# ProPrj_measure_boardd_2025-03-12.net
KiCad netlist of a schematic drawn in EasyEDA Pro
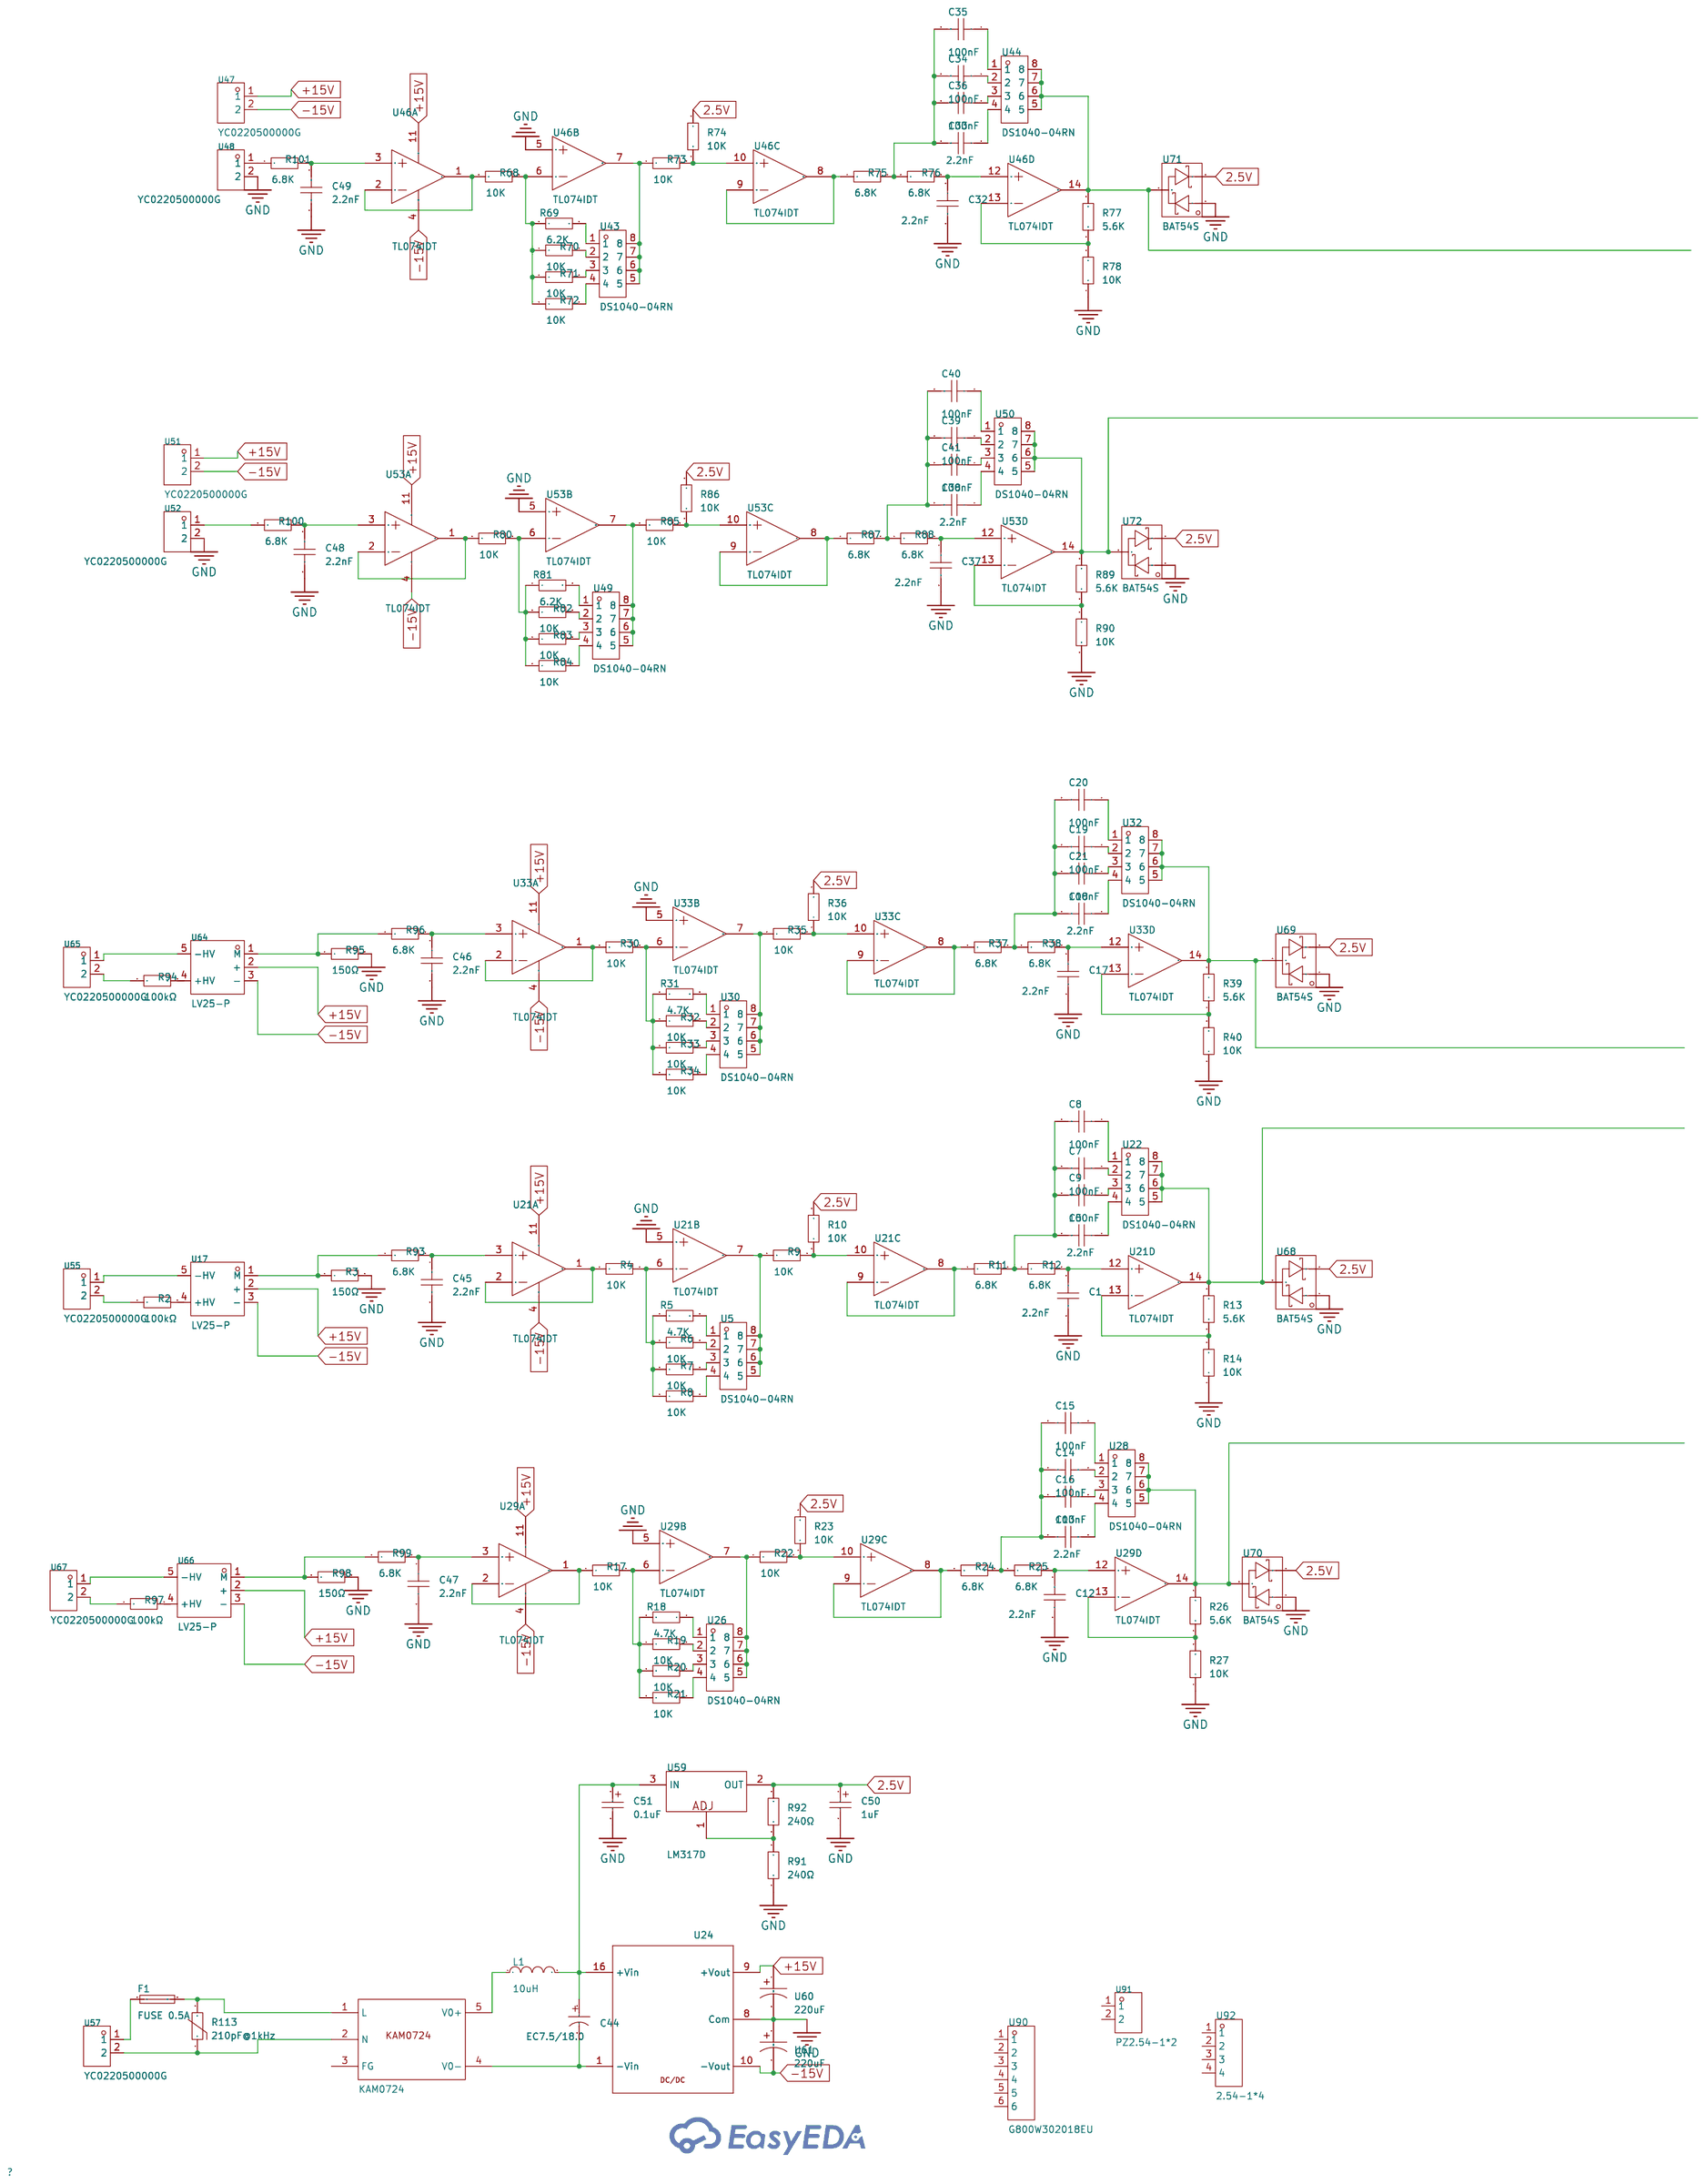
[diagram p0: schematic sheet]

(export (version "E")
  (design (tool "Eeschema 10.0.6"))
  (components
    (comp (ref "C1")
      (value "2.2nF")
      (footprint "easyedapro:C0805")
      (libsource (lib "easyedapro") (part "CAP"))
    )
    (comp (ref "C5")
      (value "2.2nF")
      (footprint "easyedapro:C0805")
      (libsource (lib "easyedapro") (part "CAP"))
    )
    (comp (ref "C7")
      (value "100nF")
      (footprint "easyedapro:C0805")
      (libsource (lib "easyedapro") (part "CAP"))
    )
    (comp (ref "C8")
      (value "100nF")
      (footprint "easyedapro:C0805")
      (libsource (lib "easyedapro") (part "CAP"))
    )
    (comp (ref "C9")
      (value "100nF")
      (footprint "easyedapro:C0805")
      (libsource (lib "easyedapro") (part "CAP"))
    )
    (comp (ref "C12")
      (value "2.2nF")
      (footprint "easyedapro:C0805")
      (libsource (lib "easyedapro") (part "CAP"))
    )
    (comp (ref "C13")
      (value "2.2nF")
      (footprint "easyedapro:C0805")
      (libsource (lib "easyedapro") (part "CAP"))
    )
    (comp (ref "C14")
      (value "100nF")
      (footprint "easyedapro:C0805")
      (libsource (lib "easyedapro") (part "CAP"))
    )
    (comp (ref "C15")
      (value "100nF")
      (footprint "easyedapro:C0805")
      (libsource (lib "easyedapro") (part "CAP"))
    )
    (comp (ref "C16")
      (value "100nF")
      (footprint "easyedapro:C0805")
      (libsource (lib "easyedapro") (part "CAP"))
    )
    (comp (ref "C17")
      (value "2.2nF")
      (footprint "easyedapro:C0805")
      (libsource (lib "easyedapro") (part "CAP"))
    )
    (comp (ref "C18")
      (value "2.2nF")
      (footprint "easyedapro:C0805")
      (libsource (lib "easyedapro") (part "CAP"))
    )
    (comp (ref "C19")
      (value "100nF")
      (footprint "easyedapro:C0805")
      (libsource (lib "easyedapro") (part "CAP"))
    )
    (comp (ref "C20")
      (value "100nF")
      (footprint "easyedapro:C0805")
      (libsource (lib "easyedapro") (part "CAP"))
    )
    (comp (ref "C21")
      (value "100nF")
      (footprint "easyedapro:C0805")
      (libsource (lib "easyedapro") (part "CAP"))
    )
    (comp (ref "C32")
      (value "2.2nF")
      (footprint "easyedapro:C0805")
      (libsource (lib "easyedapro") (part "CAP"))
    )
    (comp (ref "C33")
      (value "2.2nF")
      (footprint "easyedapro:C0805")
      (libsource (lib "easyedapro") (part "CAP"))
    )
    (comp (ref "C34")
      (value "100nF")
      (footprint "easyedapro:C0805")
      (libsource (lib "easyedapro") (part "CAP"))
    )
    (comp (ref "C35")
      (value "100nF")
      (footprint "easyedapro:C0805")
      (libsource (lib "easyedapro") (part "CAP"))
    )
    (comp (ref "C36")
      (value "100nF")
      (footprint "easyedapro:C0805")
      (libsource (lib "easyedapro") (part "CAP"))
    )
    (comp (ref "C37")
      (value "2.2nF")
      (footprint "easyedapro:C0805")
      (libsource (lib "easyedapro") (part "CAP"))
    )
    (comp (ref "C38")
      (value "2.2nF")
      (footprint "easyedapro:C0805")
      (libsource (lib "easyedapro") (part "CAP"))
    )
    (comp (ref "C39")
      (value "100nF")
      (footprint "easyedapro:C0805")
      (libsource (lib "easyedapro") (part "CAP"))
    )
    (comp (ref "C40")
      (value "100nF")
      (footprint "easyedapro:C0805")
      (libsource (lib "easyedapro") (part "CAP"))
    )
    (comp (ref "C41")
      (value "100nF")
      (footprint "easyedapro:C0805")
      (libsource (lib "easyedapro") (part "CAP"))
    )
    (comp (ref "C44")
      (value "EC7.5/18.0")
      (footprint "easyedapro:CAP-TH_BD18.0-P7.50-D1.2-FD")
      (libsource (lib "easyedapro") (part "EC7.5/18.0"))
    )
    (comp (ref "C45")
      (value "2.2nF")
      (footprint "easyedapro:C0805")
      (libsource (lib "easyedapro") (part "CAP"))
    )
    (comp (ref "C46")
      (value "2.2nF")
      (footprint "easyedapro:C0805")
      (libsource (lib "easyedapro") (part "CAP"))
    )
    (comp (ref "C47")
      (value "2.2nF")
      (footprint "easyedapro:C0805")
      (libsource (lib "easyedapro") (part "CAP"))
    )
    (comp (ref "C48")
      (value "2.2nF")
      (footprint "easyedapro:C0805")
      (libsource (lib "easyedapro") (part "CAP"))
    )
    (comp (ref "C49")
      (value "2.2nF")
      (footprint "easyedapro:C0805")
      (libsource (lib "easyedapro") (part "CAP"))
    )
    (comp (ref "C50")
      (value "1uF")
      (footprint "easyedapro:CAP-SMD_BD4.0-L4.3-W4.3-FD")
      (libsource (lib "easyedapro") (part "C_Ele_SMD"))
    )
    (comp (ref "C51")
      (value "0.1uF")
      (footprint "easyedapro:CAP-SMD_BD4.0-L4.3-W4.3-FD")
      (libsource (lib "easyedapro") (part "C_Ele_SMD"))
    )
    (comp (ref "F1")
      (value "FUSE 0.5A")
      (footprint "easyedapro:FUSE-TH_L8.5-W4.0-P5.08-D0.6")
      (fields (field (name "Manufacturer Part") "SQT3.15M") (field (name "Manufacturer") "TLC(竞沃)"))
      (libsource (lib "easyedapro") (part "FUSE 0.5A"))
    )
    (comp (ref "L1") (value "10uH") (footprint "easyedapro:L0805") (libsource (lib "easyedapro") (part "电感")))
    (comp (ref "R2")
      (value "100kΩ")
      (footprint "easyedapro:RES-TH_BD8.0-L24.5-P28.50-D0.8")
      (libsource (lib "easyedapro") (part "Res"))
    )
    (comp (ref "R3")
      (value "150Ω")
      (footprint "easyedapro:RES-TH_BD8.0-L24.5-P28.50-D0.8")
      (libsource (lib "easyedapro") (part "Res"))
    )
    (comp (ref "R4")
      (value "10K")
      (footprint "easyedapro:RES-TH_BD8.0-L24.5-P28.50-D0.8")
      (libsource (lib "easyedapro") (part "Res"))
    )
    (comp (ref "R5")
      (value "4.7K")
      (footprint "easyedapro:RES-TH_BD8.0-L24.5-P28.50-D0.8")
      (libsource (lib "easyedapro") (part "Res"))
    )
    (comp (ref "R6")
      (value "10K")
      (footprint "easyedapro:RES-TH_BD8.0-L24.5-P28.50-D0.8")
      (libsource (lib "easyedapro") (part "Res"))
    )
    (comp (ref "R7")
      (value "10K")
      (footprint "easyedapro:RES-TH_BD8.0-L24.5-P28.50-D0.8")
      (libsource (lib "easyedapro") (part "Res"))
    )
    (comp (ref "R8")
      (value "10K")
      (footprint "easyedapro:RES-TH_BD8.0-L24.5-P28.50-D0.8")
      (libsource (lib "easyedapro") (part "Res"))
    )
    (comp (ref "R9")
      (value "10K")
      (footprint "easyedapro:RES-TH_BD8.0-L24.5-P28.50-D0.8")
      (libsource (lib "easyedapro") (part "Res"))
    )
    (comp (ref "R10")
      (value "10K")
      (footprint "easyedapro:RES-TH_BD8.0-L24.5-P28.50-D0.8")
      (libsource (lib "easyedapro") (part "Res"))
    )
    (comp (ref "R11")
      (value "6.8K")
      (footprint "easyedapro:RES-TH_BD8.0-L24.5-P28.50-D0.8")
      (libsource (lib "easyedapro") (part "Res"))
    )
    (comp (ref "R12")
      (value "6.8K")
      (footprint "easyedapro:RES-TH_BD8.0-L24.5-P28.50-D0.8")
      (libsource (lib "easyedapro") (part "Res"))
    )
    (comp (ref "R13")
      (value "5.6K")
      (footprint "easyedapro:RES-TH_BD8.0-L24.5-P28.50-D0.8")
      (libsource (lib "easyedapro") (part "Res"))
    )
    (comp (ref "R14")
      (value "10K")
      (footprint "easyedapro:RES-TH_BD8.0-L24.5-P28.50-D0.8")
      (libsource (lib "easyedapro") (part "Res"))
    )
    (comp (ref "R17")
      (value "10K")
      (footprint "easyedapro:RES-TH_BD8.0-L24.5-P28.50-D0.8")
      (libsource (lib "easyedapro") (part "Res"))
    )
    (comp (ref "R18")
      (value "4.7K")
      (footprint "easyedapro:RES-TH_BD8.0-L24.5-P28.50-D0.8")
      (libsource (lib "easyedapro") (part "Res"))
    )
    (comp (ref "R19")
      (value "10K")
      (footprint "easyedapro:RES-TH_BD8.0-L24.5-P28.50-D0.8")
      (libsource (lib "easyedapro") (part "Res"))
    )
    (comp (ref "R20")
      (value "10K")
      (footprint "easyedapro:RES-TH_BD8.0-L24.5-P28.50-D0.8")
      (libsource (lib "easyedapro") (part "Res"))
    )
    (comp (ref "R21")
      (value "10K")
      (footprint "easyedapro:RES-TH_BD8.0-L24.5-P28.50-D0.8")
      (libsource (lib "easyedapro") (part "Res"))
    )
    (comp (ref "R22")
      (value "10K")
      (footprint "easyedapro:RES-TH_BD8.0-L24.5-P28.50-D0.8")
      (libsource (lib "easyedapro") (part "Res"))
    )
    (comp (ref "R23")
      (value "10K")
      (footprint "easyedapro:RES-TH_BD8.0-L24.5-P28.50-D0.8")
      (libsource (lib "easyedapro") (part "Res"))
    )
    (comp (ref "R24")
      (value "6.8K")
      (footprint "easyedapro:RES-TH_BD8.0-L24.5-P28.50-D0.8")
      (libsource (lib "easyedapro") (part "Res"))
    )
    (comp (ref "R25")
      (value "6.8K")
      (footprint "easyedapro:RES-TH_BD8.0-L24.5-P28.50-D0.8")
      (libsource (lib "easyedapro") (part "Res"))
    )
    (comp (ref "R26")
      (value "5.6K")
      (footprint "easyedapro:RES-TH_BD8.0-L24.5-P28.50-D0.8")
      (libsource (lib "easyedapro") (part "Res"))
    )
    (comp (ref "R27")
      (value "10K")
      (footprint "easyedapro:RES-TH_BD8.0-L24.5-P28.50-D0.8")
      (libsource (lib "easyedapro") (part "Res"))
    )
    (comp (ref "R30")
      (value "10K")
      (footprint "easyedapro:RES-TH_BD8.0-L24.5-P28.50-D0.8")
      (libsource (lib "easyedapro") (part "Res"))
    )
    (comp (ref "R31")
      (value "4.7K")
      (footprint "easyedapro:RES-TH_BD8.0-L24.5-P28.50-D0.8")
      (libsource (lib "easyedapro") (part "Res"))
    )
    (comp (ref "R32")
      (value "10K")
      (footprint "easyedapro:RES-TH_BD8.0-L24.5-P28.50-D0.8")
      (libsource (lib "easyedapro") (part "Res"))
    )
    (comp (ref "R33")
      (value "10K")
      (footprint "easyedapro:RES-TH_BD8.0-L24.5-P28.50-D0.8")
      (libsource (lib "easyedapro") (part "Res"))
    )
    (comp (ref "R34")
      (value "10K")
      (footprint "easyedapro:RES-TH_BD8.0-L24.5-P28.50-D0.8")
      (libsource (lib "easyedapro") (part "Res"))
    )
    (comp (ref "R35")
      (value "10K")
      (footprint "easyedapro:RES-TH_BD8.0-L24.5-P28.50-D0.8")
      (libsource (lib "easyedapro") (part "Res"))
    )
    (comp (ref "R36")
      (value "10K")
      (footprint "easyedapro:RES-TH_BD8.0-L24.5-P28.50-D0.8")
      (libsource (lib "easyedapro") (part "Res"))
    )
    (comp (ref "R37")
      (value "6.8K")
      (footprint "easyedapro:RES-TH_BD8.0-L24.5-P28.50-D0.8")
      (libsource (lib "easyedapro") (part "Res"))
    )
    (comp (ref "R38")
      (value "6.8K")
      (footprint "easyedapro:RES-TH_BD8.0-L24.5-P28.50-D0.8")
      (libsource (lib "easyedapro") (part "Res"))
    )
    (comp (ref "R39")
      (value "5.6K")
      (footprint "easyedapro:RES-TH_BD8.0-L24.5-P28.50-D0.8")
      (libsource (lib "easyedapro") (part "Res"))
    )
    (comp (ref "R40")
      (value "10K")
      (footprint "easyedapro:RES-TH_BD8.0-L24.5-P28.50-D0.8")
      (libsource (lib "easyedapro") (part "Res"))
    )
    (comp (ref "R68")
      (value "10K")
      (footprint "easyedapro:RES-TH_BD8.0-L24.5-P28.50-D0.8")
      (libsource (lib "easyedapro") (part "Res"))
    )
    (comp (ref "R69")
      (value "6.2K")
      (footprint "easyedapro:RES-TH_BD8.0-L24.5-P28.50-D0.8")
      (libsource (lib "easyedapro") (part "Res"))
    )
    (comp (ref "R70")
      (value "10K")
      (footprint "easyedapro:RES-TH_BD8.0-L24.5-P28.50-D0.8")
      (libsource (lib "easyedapro") (part "Res"))
    )
    (comp (ref "R71")
      (value "10K")
      (footprint "easyedapro:RES-TH_BD8.0-L24.5-P28.50-D0.8")
      (libsource (lib "easyedapro") (part "Res"))
    )
    (comp (ref "R72")
      (value "10K")
      (footprint "easyedapro:RES-TH_BD8.0-L24.5-P28.50-D0.8")
      (libsource (lib "easyedapro") (part "Res"))
    )
    (comp (ref "R73")
      (value "10K")
      (footprint "easyedapro:RES-TH_BD8.0-L24.5-P28.50-D0.8")
      (libsource (lib "easyedapro") (part "Res"))
    )
    (comp (ref "R74")
      (value "10K")
      (footprint "easyedapro:RES-TH_BD8.0-L24.5-P28.50-D0.8")
      (libsource (lib "easyedapro") (part "Res"))
    )
    (comp (ref "R75")
      (value "6.8K")
      (footprint "easyedapro:RES-TH_BD8.0-L24.5-P28.50-D0.8")
      (libsource (lib "easyedapro") (part "Res"))
    )
    (comp (ref "R76")
      (value "6.8K")
      (footprint "easyedapro:RES-TH_BD8.0-L24.5-P28.50-D0.8")
      (libsource (lib "easyedapro") (part "Res"))
    )
    (comp (ref "R77")
      (value "5.6K")
      (footprint "easyedapro:RES-TH_BD8.0-L24.5-P28.50-D0.8")
      (libsource (lib "easyedapro") (part "Res"))
    )
    (comp (ref "R78")
      (value "10K")
      (footprint "easyedapro:RES-TH_BD8.0-L24.5-P28.50-D0.8")
      (libsource (lib "easyedapro") (part "Res"))
    )
    (comp (ref "R80")
      (value "10K")
      (footprint "easyedapro:RES-TH_BD8.0-L24.5-P28.50-D0.8")
      (libsource (lib "easyedapro") (part "Res"))
    )
    (comp (ref "R81")
      (value "6.2K")
      (footprint "easyedapro:RES-TH_BD8.0-L24.5-P28.50-D0.8")
      (libsource (lib "easyedapro") (part "Res"))
    )
    (comp (ref "R82")
      (value "10K")
      (footprint "easyedapro:RES-TH_BD8.0-L24.5-P28.50-D0.8")
      (libsource (lib "easyedapro") (part "Res"))
    )
    (comp (ref "R83")
      (value "10K")
      (footprint "easyedapro:RES-TH_BD8.0-L24.5-P28.50-D0.8")
      (libsource (lib "easyedapro") (part "Res"))
    )
    (comp (ref "R84")
      (value "10K")
      (footprint "easyedapro:RES-TH_BD8.0-L24.5-P28.50-D0.8")
      (libsource (lib "easyedapro") (part "Res"))
    )
    (comp (ref "R85")
      (value "10K")
      (footprint "easyedapro:RES-TH_BD8.0-L24.5-P28.50-D0.8")
      (libsource (lib "easyedapro") (part "Res"))
    )
    (comp (ref "R86")
      (value "10K")
      (footprint "easyedapro:RES-TH_BD8.0-L24.5-P28.50-D0.8")
      (libsource (lib "easyedapro") (part "Res"))
    )
    (comp (ref "R87")
      (value "6.8K")
      (footprint "easyedapro:RES-TH_BD8.0-L24.5-P28.50-D0.8")
      (libsource (lib "easyedapro") (part "Res"))
    )
    (comp (ref "R88")
      (value "6.8K")
      (footprint "easyedapro:RES-TH_BD8.0-L24.5-P28.50-D0.8")
      (libsource (lib "easyedapro") (part "Res"))
    )
    (comp (ref "R89")
      (value "5.6K")
      (footprint "easyedapro:RES-TH_BD8.0-L24.5-P28.50-D0.8")
      (libsource (lib "easyedapro") (part "Res"))
    )
    (comp (ref "R90")
      (value "10K")
      (footprint "easyedapro:RES-TH_BD8.0-L24.5-P28.50-D0.8")
      (libsource (lib "easyedapro") (part "Res"))
    )
    (comp (ref "R91")
      (value "240Ω")
      (footprint "easyedapro:RES-TH_BD8.0-L24.5-P28.50-D0.8")
      (libsource (lib "easyedapro") (part "Res"))
    )
    (comp (ref "R92")
      (value "240Ω")
      (footprint "easyedapro:RES-TH_BD8.0-L24.5-P28.50-D0.8")
      (libsource (lib "easyedapro") (part "Res"))
    )
    (comp (ref "R93")
      (value "6.8K")
      (footprint "easyedapro:RES-TH_BD8.0-L24.5-P28.50-D0.8")
      (libsource (lib "easyedapro") (part "Res"))
    )
    (comp (ref "R94")
      (value "100kΩ")
      (footprint "easyedapro:RES-TH_BD8.0-L24.5-P28.50-D0.8")
      (libsource (lib "easyedapro") (part "Res"))
    )
    (comp (ref "R95")
      (value "150Ω")
      (footprint "easyedapro:RES-TH_BD8.0-L24.5-P28.50-D0.8")
      (libsource (lib "easyedapro") (part "Res"))
    )
    (comp (ref "R96")
      (value "6.8K")
      (footprint "easyedapro:RES-TH_BD8.0-L24.5-P28.50-D0.8")
      (libsource (lib "easyedapro") (part "Res"))
    )
    (comp (ref "R97")
      (value "100kΩ")
      (footprint "easyedapro:RES-TH_BD8.0-L24.5-P28.50-D0.8")
      (libsource (lib "easyedapro") (part "Res"))
    )
    (comp (ref "R98")
      (value "150Ω")
      (footprint "easyedapro:RES-TH_BD8.0-L24.5-P28.50-D0.8")
      (libsource (lib "easyedapro") (part "Res"))
    )
    (comp (ref "R99")
      (value "6.8K")
      (footprint "easyedapro:RES-TH_BD8.0-L24.5-P28.50-D0.8")
      (libsource (lib "easyedapro") (part "Res"))
    )
    (comp (ref "R100")
      (value "6.8K")
      (footprint "easyedapro:RES-TH_BD8.0-L24.5-P28.50-D0.8")
      (libsource (lib "easyedapro") (part "Res"))
    )
    (comp (ref "R101")
      (value "6.8K")
      (footprint "easyedapro:RES-TH_BD8.0-L24.5-P28.50-D0.8")
      (libsource (lib "easyedapro") (part "Res"))
    )
    (comp (ref "R113")
      (value "210pF@1kHz")
      (footprint "easyedapro:RES-TH_L12.5-W5.1-P7.50-D1.2-S2.20")
      (fields (field (name "Manufacturer Part") "VDR-10D471K") (field (name "Manufacturer") "VDR(嵩隆)"))
      (libsource (lib "easyedapro") (part "VDR-10D471K"))
    )
    (comp (ref "U5")
      (value "DS1040-04RN")
      (footprint "easyedapro:KEY-TH_DS1040-04RN")
      (description "Number of Positions:4Bit Lead Pitch:2.54mm Color:Red")
      (fields (field (name "Manufacturer") "CONNFLY"))
      (libsource (lib "easyedapro") (part "DS1040-04RN"))
    )
    (comp (ref "U17")
      (value "LV25-P")
      (footprint "easyedapro:SENSOR-TH_LV25-P")
      (fields (field (name "Manufacturer") "LEM(莱姆)"))
      (libsource (lib "easyedapro") (part "LV25-P"))
    )
    (comp (ref "U21")
      (value "TL074IDT")
      (footprint "easyedapro:SOIC-14_L8.7-W3.9-P1.27-LS6.0-BL")
      (fields (field (name "Manufacturer") "ST(意法半导体)"))
      (libsource (lib "easyedapro") (part "TL074IDT"))
    )
    (comp (ref "U22")
      (value "DS1040-04RN")
      (footprint "easyedapro:KEY-TH_DS1040-04RN")
      (description "Number of Positions:4Bit Lead Pitch:2.54mm Color:Red")
      (fields (field (name "Manufacturer") "CONNFLY"))
      (libsource (lib "easyedapro") (part "DS1040-04RN"))
    )
    (comp (ref "U24")
      (value "~")
      (footprint "easyedapro:TEL_8_SERIES")
      (libsource (lib "easyedapro") (part "TEL_8-2423"))
    )
    (comp (ref "U26")
      (value "DS1040-04RN")
      (footprint "easyedapro:KEY-TH_DS1040-04RN")
      (description "Number of Positions:4Bit Lead Pitch:2.54mm Color:Red")
      (fields (field (name "Manufacturer") "CONNFLY"))
      (libsource (lib "easyedapro") (part "DS1040-04RN"))
    )
    (comp (ref "U28")
      (value "DS1040-04RN")
      (footprint "easyedapro:KEY-TH_DS1040-04RN")
      (description "Number of Positions:4Bit Lead Pitch:2.54mm Color:Red")
      (fields (field (name "Manufacturer") "CONNFLY"))
      (libsource (lib "easyedapro") (part "DS1040-04RN"))
    )
    (comp (ref "U29")
      (value "TL074IDT")
      (footprint "easyedapro:SOIC-14_L8.7-W3.9-P1.27-LS6.0-BL")
      (fields (field (name "Manufacturer") "ST(意法半导体)"))
      (libsource (lib "easyedapro") (part "TL074IDT"))
    )
    (comp (ref "U30")
      (value "DS1040-04RN")
      (footprint "easyedapro:KEY-TH_DS1040-04RN")
      (description "Number of Positions:4Bit Lead Pitch:2.54mm Color:Red")
      (fields (field (name "Manufacturer") "CONNFLY"))
      (libsource (lib "easyedapro") (part "DS1040-04RN"))
    )
    (comp (ref "U32")
      (value "DS1040-04RN")
      (footprint "easyedapro:KEY-TH_DS1040-04RN")
      (description "Number of Positions:4Bit Lead Pitch:2.54mm Color:Red")
      (fields (field (name "Manufacturer") "CONNFLY"))
      (libsource (lib "easyedapro") (part "DS1040-04RN"))
    )
    (comp (ref "U33")
      (value "TL074IDT")
      (footprint "easyedapro:SOIC-14_L8.7-W3.9-P1.27-LS6.0-BL")
      (fields (field (name "Manufacturer") "ST(意法半导体)"))
      (libsource (lib "easyedapro") (part "TL074IDT"))
    )
    (comp (ref "U43")
      (value "DS1040-04RN")
      (footprint "easyedapro:KEY-TH_DS1040-04RN")
      (description "Number of Positions:4Bit Lead Pitch:2.54mm Color:Red")
      (fields (field (name "Manufacturer") "CONNFLY"))
      (libsource (lib "easyedapro") (part "DS1040-04RN"))
    )
    (comp (ref "U44")
      (value "DS1040-04RN")
      (footprint "easyedapro:KEY-TH_DS1040-04RN")
      (description "Number of Positions:4Bit Lead Pitch:2.54mm Color:Red")
      (fields (field (name "Manufacturer") "CONNFLY"))
      (libsource (lib "easyedapro") (part "DS1040-04RN"))
    )
    (comp (ref "U46")
      (value "TL074IDT")
      (footprint "easyedapro:SOIC-14_L8.7-W3.9-P1.27-LS6.0-BL")
      (fields (field (name "Manufacturer") "ST(意法半导体)"))
      (libsource (lib "easyedapro") (part "TL074IDT"))
    )
    (comp (ref "U47")
      (value "YC0220500000G")
      (footprint "easyedapro:CONN-TH_YC0220500000G")
      (fields (field (name "Manufacturer") "Amphenol"))
      (libsource (lib "easyedapro") (part "YC0220500000G"))
    )
    (comp (ref "U48")
      (value "YC0220500000G")
      (footprint "easyedapro:CONN-TH_YC0220500000G")
      (fields (field (name "Manufacturer") "Amphenol"))
      (libsource (lib "easyedapro") (part "YC0220500000G"))
    )
    (comp (ref "U49")
      (value "DS1040-04RN")
      (footprint "easyedapro:KEY-TH_DS1040-04RN")
      (description "Number of Positions:4Bit Lead Pitch:2.54mm Color:Red")
      (fields (field (name "Manufacturer") "CONNFLY"))
      (libsource (lib "easyedapro") (part "DS1040-04RN"))
    )
    (comp (ref "U50")
      (value "DS1040-04RN")
      (footprint "easyedapro:KEY-TH_DS1040-04RN")
      (description "Number of Positions:4Bit Lead Pitch:2.54mm Color:Red")
      (fields (field (name "Manufacturer") "CONNFLY"))
      (libsource (lib "easyedapro") (part "DS1040-04RN"))
    )
    (comp (ref "U51")
      (value "YC0220500000G")
      (footprint "easyedapro:CONN-TH_YC0220500000G")
      (fields (field (name "Manufacturer") "Amphenol"))
      (libsource (lib "easyedapro") (part "YC0220500000G"))
    )
    (comp (ref "U52")
      (value "YC0220500000G")
      (footprint "easyedapro:CONN-TH_YC0220500000G")
      (fields (field (name "Manufacturer") "Amphenol"))
      (libsource (lib "easyedapro") (part "YC0220500000G"))
    )
    (comp (ref "U53")
      (value "TL074IDT")
      (footprint "easyedapro:SOIC-14_L8.7-W3.9-P1.27-LS6.0-BL")
      (fields (field (name "Manufacturer") "ST(意法半导体)"))
      (libsource (lib "easyedapro") (part "TL074IDT"))
    )
    (comp (ref "U55")
      (value "YC0220500000G")
      (footprint "easyedapro:CONN-TH_YC0220500000G")
      (fields (field (name "Manufacturer") "Amphenol"))
      (libsource (lib "easyedapro") (part "YC0220500000G"))
    )
    (comp (ref "U57")
      (value "YC0220500000G")
      (footprint "easyedapro:CONN-TH_YC0220500000G")
      (fields (field (name "Manufacturer") "Amphenol"))
      (libsource (lib "easyedapro") (part "YC0220500000G"))
    )
    (comp (ref "U59")
      (value "LM317D")
      (footprint "easyedapro:TO-252-2_L6.6-W6.1-P4.57-LS9.9-BR-CW")
      (fields (field (name "Manufacturer") "YFW(佑风微)"))
      (libsource (lib "easyedapro") (part "LM317D"))
    )
    (comp (ref "U60")
      (value "220uF")
      (footprint "easyedapro:CAP-TH_BD6.3-P2.50-D0.6-FD")
      (fields (field (name "Manufacturer Part") "25V220uF CD288") (field (name "Manufacturer") "HRK(鸿瑞凯电子)"))
      (libsource (lib "easyedapro") (part "25V220UF CD288"))
    )
    (comp (ref "U61")
      (value "220uF")
      (footprint "easyedapro:CAP-TH_BD6.3-P2.50-D0.6-FD")
      (fields (field (name "Manufacturer Part") "25V220uF CD288") (field (name "Manufacturer") "HRK(鸿瑞凯电子)"))
      (libsource (lib "easyedapro") (part "25V220UF CD288"))
    )
    (comp (ref "U62")
      (value "KAM0724")
      (footprint "easyedapro:KAM0724")
      (libsource (lib "easyedapro") (part "KAM0724"))
    )
    (comp (ref "U64")
      (value "LV25-P")
      (footprint "easyedapro:SENSOR-TH_LV25-P")
      (fields (field (name "Manufacturer") "LEM(莱姆)"))
      (libsource (lib "easyedapro") (part "LV25-P"))
    )
    (comp (ref "U65")
      (value "YC0220500000G")
      (footprint "easyedapro:CONN-TH_YC0220500000G")
      (fields (field (name "Manufacturer") "Amphenol"))
      (libsource (lib "easyedapro") (part "YC0220500000G"))
    )
    (comp (ref "U66")
      (value "LV25-P")
      (footprint "easyedapro:SENSOR-TH_LV25-P")
      (fields (field (name "Manufacturer") "LEM(莱姆)"))
      (libsource (lib "easyedapro") (part "LV25-P"))
    )
    (comp (ref "U67")
      (value "YC0220500000G")
      (footprint "easyedapro:CONN-TH_YC0220500000G")
      (fields (field (name "Manufacturer") "Amphenol"))
      (libsource (lib "easyedapro") (part "YC0220500000G"))
    )
    (comp (ref "U68")
      (value "BAT54S")
      (footprint "easyedapro:SOT-23-3_L2.9-W1.3-P1.90-LS2.4-BR")
      (fields (field (name "Manufacturer") "DOWO(东沃)"))
      (libsource (lib "easyedapro") (part "BAT54S_C22374724"))
    )
    (comp (ref "U69")
      (value "BAT54S")
      (footprint "easyedapro:SOT-23-3_L2.9-W1.3-P1.90-LS2.4-BR")
      (fields (field (name "Manufacturer") "DOWO(东沃)"))
      (libsource (lib "easyedapro") (part "BAT54S_C22374724"))
    )
    (comp (ref "U70")
      (value "BAT54S")
      (footprint "easyedapro:SOT-23-3_L2.9-W1.3-P1.90-LS2.4-BR")
      (fields (field (name "Manufacturer") "DOWO(东沃)"))
      (libsource (lib "easyedapro") (part "BAT54S_C22374724"))
    )
    (comp (ref "U71")
      (value "BAT54S")
      (footprint "easyedapro:SOT-23-3_L2.9-W1.3-P1.90-LS2.4-BR")
      (fields (field (name "Manufacturer") "DOWO(东沃)"))
      (libsource (lib "easyedapro") (part "BAT54S_C22374724"))
    )
    (comp (ref "U72")
      (value "BAT54S")
      (footprint "easyedapro:SOT-23-3_L2.9-W1.3-P1.90-LS2.4-BR")
      (fields (field (name "Manufacturer") "DOWO(东沃)"))
      (libsource (lib "easyedapro") (part "BAT54S_C22374724"))
    )
    (comp (ref "U90")
      (value "G800W302018EU")
      (footprint "easyedapro:HDR-TH_6P-P2.54-V-M")
      (description "Pin Structure:1x6P Pitch:2.54mm Number of Rows:Single Row Number of Pins:6P")
      (fields (field (name "Manufacturer") "Amphenol"))
      (libsource (lib "easyedapro") (part "G800W302018EU"))
    )
    (comp (ref "U91")
      (value "PZ2.54-1*2")
      (footprint "easyedapro:HDR-TH_2P-P2.54-V-M-3")
      (fields (field (name "Manufacturer") "ZHOURI(洲日)"))
      (libsource (lib "easyedapro") (part "PZ2.54-1*2"))
    )
    (comp (ref "U92")
      (value "2.54-1*4")
      (footprint "easyedapro:HDR-TH_4P-P2.54-V-M-1")
      (description "Pin Structure:1x4P Pitch:2.54mm Number of Rows:Plugin Number of Pins:4P")
      (fields (field (name "Manufacturer") "ZHOURI(洲日)"))
      (libsource (lib "easyedapro") (part "2.54-1*4"))
    )
  )
  (nets
    (net (code "1") (name "+15V") (class "Default")
      (node (ref "U17") (pin "2") (pinfunction "+_2") (pintype "input"))
      (node (ref "U21") (pin "11") (pinfunction "VCC-_11") (pintype "unspecified"))
      (node (ref "U24") (pin "9") (pinfunction "+Vout_9") (pintype "unspecified"))
      (node (ref "U29") (pin "11") (pinfunction "VCC-_11") (pintype "unspecified"))
      (node (ref "U33") (pin "11") (pinfunction "VCC-_11") (pintype "unspecified"))
      (node (ref "U46") (pin "11") (pinfunction "VCC-_11") (pintype "unspecified"))
      (node (ref "U47") (pin "1") (pinfunction "1_1") (pintype "input"))
      (node (ref "U51") (pin "1") (pinfunction "1_1") (pintype "input"))
      (node (ref "U53") (pin "11") (pinfunction "VCC-_11") (pintype "unspecified"))
      (node (ref "U60") (pin "1") (pinfunction "1_1") (pintype "unspecified"))
      (node (ref "U64") (pin "2") (pinfunction "+_2") (pintype "input"))
      (node (ref "U66") (pin "2") (pinfunction "+_2") (pintype "input"))
    )
    (net (code "2") (name "-15V") (class "Default")
      (node (ref "U17") (pin "3") (pinfunction "-_3") (pintype "input"))
      (node (ref "U21") (pin "4") (pinfunction "VCC+_4") (pintype "unspecified"))
      (node (ref "U24") (pin "10") (pinfunction "-Vout_10") (pintype "unspecified"))
      (node (ref "U29") (pin "4") (pinfunction "VCC+_4") (pintype "unspecified"))
      (node (ref "U33") (pin "4") (pinfunction "VCC+_4") (pintype "unspecified"))
      (node (ref "U46") (pin "4") (pinfunction "VCC+_4") (pintype "unspecified"))
      (node (ref "U47") (pin "2") (pinfunction "2_2") (pintype "input"))
      (node (ref "U51") (pin "2") (pinfunction "2_2") (pintype "input"))
      (node (ref "U53") (pin "4") (pinfunction "VCC+_4") (pintype "unspecified"))
      (node (ref "U61") (pin "2") (pinfunction "2_2") (pintype "unspecified"))
      (node (ref "U64") (pin "3") (pinfunction "-_3") (pintype "input"))
      (node (ref "U66") (pin "3") (pinfunction "-_3") (pintype "input"))
    )
    (net (code "3") (name "2.5V") (class "Default")
      (node (ref "C50") (pin "1") (pinfunction "1_1") (pintype "input"))
      (node (ref "R10") (pin "2") (pinfunction "2_2") (pintype "input"))
      (node (ref "R23") (pin "2") (pinfunction "2_2") (pintype "input"))
      (node (ref "R36") (pin "2") (pinfunction "2_2") (pintype "input"))
      (node (ref "R74") (pin "2") (pinfunction "2_2") (pintype "input"))
      (node (ref "R86") (pin "2") (pinfunction "2_2") (pintype "input"))
      (node (ref "R92") (pin "2") (pinfunction "2_2") (pintype "input"))
      (node (ref "U59") (pin "2") (pinfunction "OUT_2") (pintype "unspecified"))
      (node (ref "U68") (pin "2") (pinfunction "2_2") (pintype "unspecified"))
      (node (ref "U69") (pin "2") (pinfunction "2_2") (pintype "unspecified"))
      (node (ref "U70") (pin "2") (pinfunction "2_2") (pintype "unspecified"))
      (node (ref "U71") (pin "2") (pinfunction "2_2") (pintype "unspecified"))
      (node (ref "U72") (pin "2") (pinfunction "2_2") (pintype "unspecified"))
    )
    (net (code "4") (name "GND") (class "Default")
      (node (ref "C1") (pin "2") (pinfunction "2_2") (pintype "input"))
      (node (ref "C12") (pin "2") (pinfunction "2_2") (pintype "input"))
      (node (ref "C17") (pin "2") (pinfunction "2_2") (pintype "input"))
      (node (ref "C32") (pin "2") (pinfunction "2_2") (pintype "input"))
      (node (ref "C37") (pin "2") (pinfunction "2_2") (pintype "input"))
      (node (ref "C45") (pin "2") (pinfunction "2_2") (pintype "input"))
      (node (ref "C46") (pin "2") (pinfunction "2_2") (pintype "input"))
      (node (ref "C47") (pin "2") (pinfunction "2_2") (pintype "input"))
      (node (ref "C48") (pin "2") (pinfunction "2_2") (pintype "input"))
      (node (ref "C49") (pin "2") (pinfunction "2_2") (pintype "input"))
      (node (ref "C50") (pin "2") (pinfunction "2_2") (pintype "input"))
      (node (ref "C51") (pin "2") (pinfunction "2_2") (pintype "input"))
      (node (ref "R14") (pin "1") (pinfunction "1_1") (pintype "input"))
      (node (ref "R27") (pin "1") (pinfunction "1_1") (pintype "input"))
      (node (ref "R3") (pin "2") (pinfunction "2_2") (pintype "input"))
      (node (ref "R40") (pin "1") (pinfunction "1_1") (pintype "input"))
      (node (ref "R78") (pin "1") (pinfunction "1_1") (pintype "input"))
      (node (ref "R90") (pin "1") (pinfunction "1_1") (pintype "input"))
      (node (ref "R91") (pin "1") (pinfunction "1_1") (pintype "input"))
      (node (ref "R95") (pin "2") (pinfunction "2_2") (pintype "input"))
      (node (ref "R98") (pin "2") (pinfunction "2_2") (pintype "input"))
      (node (ref "U21") (pin "5") (pinfunction "2IN+_5") (pintype "unspecified"))
      (node (ref "U24") (pin "8") (pinfunction "Com_8") (pintype "unspecified"))
      (node (ref "U29") (pin "5") (pinfunction "2IN+_5") (pintype "unspecified"))
      (node (ref "U33") (pin "5") (pinfunction "2IN+_5") (pintype "unspecified"))
      (node (ref "U46") (pin "5") (pinfunction "2IN+_5") (pintype "unspecified"))
      (node (ref "U48") (pin "2") (pinfunction "2_2") (pintype "input"))
      (node (ref "U52") (pin "2") (pinfunction "2_2") (pintype "input"))
      (node (ref "U53") (pin "5") (pinfunction "2IN+_5") (pintype "unspecified"))
      (node (ref "U60") (pin "2") (pinfunction "2_2") (pintype "unspecified"))
      (node (ref "U61") (pin "1") (pinfunction "1_1") (pintype "unspecified"))
      (node (ref "U68") (pin "1") (pinfunction "1_1") (pintype "unspecified"))
      (node (ref "U69") (pin "1") (pinfunction "1_1") (pintype "unspecified"))
      (node (ref "U70") (pin "1") (pinfunction "1_1") (pintype "unspecified"))
      (node (ref "U71") (pin "1") (pinfunction "1_1") (pintype "unspecified"))
      (node (ref "U72") (pin "1") (pinfunction "1_1") (pintype "unspecified"))
    )
    (net (code "5") (name "Net-(C5-Pad1)") (class "Default")
      (node (ref "C5") (pin "1") (pinfunction "1_1") (pintype "input"))
      (node (ref "U22") (pin "4") (pinfunction "4_4") (pintype "unspecified"))
    )
    (net (code "6") (name "Net-(C5-Pad2)") (class "Default")
      (node (ref "C5") (pin "2") (pinfunction "2_2") (pintype "input"))
      (node (ref "C7") (pin "2") (pinfunction "2_2") (pintype "input"))
      (node (ref "C8") (pin "2") (pinfunction "2_2") (pintype "input"))
      (node (ref "C9") (pin "2") (pinfunction "2_2") (pintype "input"))
      (node (ref "R11") (pin "2") (pinfunction "2_2") (pintype "input"))
      (node (ref "R12") (pin "1") (pinfunction "1_1") (pintype "input"))
    )
    (net (code "7") (name "Net-(C7-Pad1)") (class "Default")
      (node (ref "C7") (pin "1") (pinfunction "1_1") (pintype "input"))
      (node (ref "U22") (pin "2") (pinfunction "2_2") (pintype "unspecified"))
    )
    (net (code "8") (name "Net-(C8-Pad1)") (class "Default")
      (node (ref "C8") (pin "1") (pinfunction "1_1") (pintype "input"))
      (node (ref "U22") (pin "1") (pinfunction "1_1") (pintype "unspecified"))
    )
    (net (code "9") (name "Net-(C9-Pad1)") (class "Default")
      (node (ref "C9") (pin "1") (pinfunction "1_1") (pintype "input"))
      (node (ref "U22") (pin "3") (pinfunction "3_3") (pintype "unspecified"))
    )
    (net (code "10") (name "Net-(C13-Pad1)") (class "Default")
      (node (ref "C13") (pin "1") (pinfunction "1_1") (pintype "input"))
      (node (ref "U28") (pin "4") (pinfunction "4_4") (pintype "unspecified"))
    )
    (net (code "11") (name "Net-(C13-Pad2)") (class "Default")
      (node (ref "C13") (pin "2") (pinfunction "2_2") (pintype "input"))
      (node (ref "C14") (pin "2") (pinfunction "2_2") (pintype "input"))
      (node (ref "C15") (pin "2") (pinfunction "2_2") (pintype "input"))
      (node (ref "C16") (pin "2") (pinfunction "2_2") (pintype "input"))
      (node (ref "R24") (pin "2") (pinfunction "2_2") (pintype "input"))
      (node (ref "R25") (pin "1") (pinfunction "1_1") (pintype "input"))
    )
    (net (code "12") (name "Net-(C14-Pad1)") (class "Default")
      (node (ref "C14") (pin "1") (pinfunction "1_1") (pintype "input"))
      (node (ref "U28") (pin "2") (pinfunction "2_2") (pintype "unspecified"))
    )
    (net (code "13") (name "Net-(C15-Pad1)") (class "Default")
      (node (ref "C15") (pin "1") (pinfunction "1_1") (pintype "input"))
      (node (ref "U28") (pin "1") (pinfunction "1_1") (pintype "unspecified"))
    )
    (net (code "14") (name "Net-(C16-Pad1)") (class "Default")
      (node (ref "C16") (pin "1") (pinfunction "1_1") (pintype "input"))
      (node (ref "U28") (pin "3") (pinfunction "3_3") (pintype "unspecified"))
    )
    (net (code "15") (name "Net-(C18-Pad1)") (class "Default")
      (node (ref "C18") (pin "1") (pinfunction "1_1") (pintype "input"))
      (node (ref "U32") (pin "4") (pinfunction "4_4") (pintype "unspecified"))
    )
    (net (code "16") (name "Net-(C18-Pad2)") (class "Default")
      (node (ref "C18") (pin "2") (pinfunction "2_2") (pintype "input"))
      (node (ref "C19") (pin "2") (pinfunction "2_2") (pintype "input"))
      (node (ref "C20") (pin "2") (pinfunction "2_2") (pintype "input"))
      (node (ref "C21") (pin "2") (pinfunction "2_2") (pintype "input"))
      (node (ref "R37") (pin "2") (pinfunction "2_2") (pintype "input"))
      (node (ref "R38") (pin "1") (pinfunction "1_1") (pintype "input"))
    )
    (net (code "17") (name "Net-(C19-Pad1)") (class "Default")
      (node (ref "C19") (pin "1") (pinfunction "1_1") (pintype "input"))
      (node (ref "U32") (pin "2") (pinfunction "2_2") (pintype "unspecified"))
    )
    (net (code "18") (name "Net-(C20-Pad1)") (class "Default")
      (node (ref "C20") (pin "1") (pinfunction "1_1") (pintype "input"))
      (node (ref "U32") (pin "1") (pinfunction "1_1") (pintype "unspecified"))
    )
    (net (code "19") (name "Net-(C21-Pad1)") (class "Default")
      (node (ref "C21") (pin "1") (pinfunction "1_1") (pintype "input"))
      (node (ref "U32") (pin "3") (pinfunction "3_3") (pintype "unspecified"))
    )
    (net (code "20") (name "Net-(C33-Pad1)") (class "Default")
      (node (ref "C33") (pin "1") (pinfunction "1_1") (pintype "input"))
      (node (ref "U44") (pin "4") (pinfunction "4_4") (pintype "unspecified"))
    )
    (net (code "21") (name "Net-(C33-Pad2)") (class "Default")
      (node (ref "C33") (pin "2") (pinfunction "2_2") (pintype "input"))
      (node (ref "C34") (pin "2") (pinfunction "2_2") (pintype "input"))
      (node (ref "C35") (pin "2") (pinfunction "2_2") (pintype "input"))
      (node (ref "C36") (pin "2") (pinfunction "2_2") (pintype "input"))
      (node (ref "R75") (pin "2") (pinfunction "2_2") (pintype "input"))
      (node (ref "R76") (pin "1") (pinfunction "1_1") (pintype "input"))
    )
    (net (code "22") (name "Net-(C34-Pad1)") (class "Default")
      (node (ref "C34") (pin "1") (pinfunction "1_1") (pintype "input"))
      (node (ref "U44") (pin "2") (pinfunction "2_2") (pintype "unspecified"))
    )
    (net (code "23") (name "Net-(C35-Pad1)") (class "Default")
      (node (ref "C35") (pin "1") (pinfunction "1_1") (pintype "input"))
      (node (ref "U44") (pin "1") (pinfunction "1_1") (pintype "unspecified"))
    )
    (net (code "24") (name "Net-(C36-Pad1)") (class "Default")
      (node (ref "C36") (pin "1") (pinfunction "1_1") (pintype "input"))
      (node (ref "U44") (pin "3") (pinfunction "3_3") (pintype "unspecified"))
    )
    (net (code "25") (name "Net-(C38-Pad1)") (class "Default")
      (node (ref "C38") (pin "1") (pinfunction "1_1") (pintype "input"))
      (node (ref "U50") (pin "4") (pinfunction "4_4") (pintype "unspecified"))
    )
    (net (code "26") (name "Net-(C38-Pad2)") (class "Default")
      (node (ref "C38") (pin "2") (pinfunction "2_2") (pintype "input"))
      (node (ref "C39") (pin "2") (pinfunction "2_2") (pintype "input"))
      (node (ref "C40") (pin "2") (pinfunction "2_2") (pintype "input"))
      (node (ref "C41") (pin "2") (pinfunction "2_2") (pintype "input"))
      (node (ref "R87") (pin "2") (pinfunction "2_2") (pintype "input"))
      (node (ref "R88") (pin "1") (pinfunction "1_1") (pintype "input"))
    )
    (net (code "27") (name "Net-(C39-Pad1)") (class "Default")
      (node (ref "C39") (pin "1") (pinfunction "1_1") (pintype "input"))
      (node (ref "U50") (pin "2") (pinfunction "2_2") (pintype "unspecified"))
    )
    (net (code "28") (name "Net-(C40-Pad1)") (class "Default")
      (node (ref "C40") (pin "1") (pinfunction "1_1") (pintype "input"))
      (node (ref "U50") (pin "1") (pinfunction "1_1") (pintype "unspecified"))
    )
    (net (code "29") (name "Net-(C41-Pad1)") (class "Default")
      (node (ref "C41") (pin "1") (pinfunction "1_1") (pintype "input"))
      (node (ref "U50") (pin "3") (pinfunction "3_3") (pintype "unspecified"))
    )
    (net (code "30") (name "Net-(F1-Pad1)") (class "Default")
      (node (ref "F1") (pin "1") (pinfunction "1_1") (pintype "unspecified"))
      (node (ref "U57") (pin "1") (pinfunction "1_1") (pintype "input"))
    )
    (net (code "31") (name "Net-(R2-Pad1)") (class "Default")
      (node (ref "R2") (pin "1") (pinfunction "1_1") (pintype "input"))
      (node (ref "U55") (pin "2") (pinfunction "2_2") (pintype "input"))
    )
    (net (code "32") (name "Net-(R5-Pad2)") (class "Default")
      (node (ref "R5") (pin "2") (pinfunction "2_2") (pintype "input"))
      (node (ref "U5") (pin "1") (pinfunction "1_1") (pintype "unspecified"))
    )
    (net (code "33") (name "Net-(R6-Pad2)") (class "Default")
      (node (ref "R6") (pin "2") (pinfunction "2_2") (pintype "input"))
      (node (ref "U5") (pin "2") (pinfunction "2_2") (pintype "unspecified"))
    )
    (net (code "34") (name "Net-(R7-Pad2)") (class "Default")
      (node (ref "R7") (pin "2") (pinfunction "2_2") (pintype "input"))
      (node (ref "U5") (pin "3") (pinfunction "3_3") (pintype "unspecified"))
    )
    (net (code "35") (name "Net-(R8-Pad2)") (class "Default")
      (node (ref "R8") (pin "2") (pinfunction "2_2") (pintype "input"))
      (node (ref "U5") (pin "4") (pinfunction "4_4") (pintype "unspecified"))
    )
    (net (code "36") (name "Net-(R18-Pad2)") (class "Default")
      (node (ref "R18") (pin "2") (pinfunction "2_2") (pintype "input"))
      (node (ref "U26") (pin "1") (pinfunction "1_1") (pintype "unspecified"))
    )
    (net (code "37") (name "Net-(R19-Pad2)") (class "Default")
      (node (ref "R19") (pin "2") (pinfunction "2_2") (pintype "input"))
      (node (ref "U26") (pin "2") (pinfunction "2_2") (pintype "unspecified"))
    )
    (net (code "38") (name "Net-(R20-Pad2)") (class "Default")
      (node (ref "R20") (pin "2") (pinfunction "2_2") (pintype "input"))
      (node (ref "U26") (pin "3") (pinfunction "3_3") (pintype "unspecified"))
    )
    (net (code "39") (name "Net-(R21-Pad2)") (class "Default")
      (node (ref "R21") (pin "2") (pinfunction "2_2") (pintype "input"))
      (node (ref "U26") (pin "4") (pinfunction "4_4") (pintype "unspecified"))
    )
    (net (code "40") (name "Net-(R31-Pad2)") (class "Default")
      (node (ref "R31") (pin "2") (pinfunction "2_2") (pintype "input"))
      (node (ref "U30") (pin "1") (pinfunction "1_1") (pintype "unspecified"))
    )
    (net (code "41") (name "Net-(R32-Pad2)") (class "Default")
      (node (ref "R32") (pin "2") (pinfunction "2_2") (pintype "input"))
      (node (ref "U30") (pin "2") (pinfunction "2_2") (pintype "unspecified"))
    )
    (net (code "42") (name "Net-(R33-Pad2)") (class "Default")
      (node (ref "R33") (pin "2") (pinfunction "2_2") (pintype "input"))
      (node (ref "U30") (pin "3") (pinfunction "3_3") (pintype "unspecified"))
    )
    (net (code "43") (name "Net-(R34-Pad2)") (class "Default")
      (node (ref "R34") (pin "2") (pinfunction "2_2") (pintype "input"))
      (node (ref "U30") (pin "4") (pinfunction "4_4") (pintype "unspecified"))
    )
    (net (code "44") (name "Net-(R69-Pad2)") (class "Default")
      (node (ref "R69") (pin "2") (pinfunction "2_2") (pintype "input"))
      (node (ref "U43") (pin "1") (pinfunction "1_1") (pintype "unspecified"))
    )
    (net (code "45") (name "Net-(R70-Pad2)") (class "Default")
      (node (ref "R70") (pin "2") (pinfunction "2_2") (pintype "input"))
      (node (ref "U43") (pin "2") (pinfunction "2_2") (pintype "unspecified"))
    )
    (net (code "46") (name "Net-(R71-Pad2)") (class "Default")
      (node (ref "R71") (pin "2") (pinfunction "2_2") (pintype "input"))
      (node (ref "U43") (pin "3") (pinfunction "3_3") (pintype "unspecified"))
    )
    (net (code "47") (name "Net-(R72-Pad2)") (class "Default")
      (node (ref "R72") (pin "2") (pinfunction "2_2") (pintype "input"))
      (node (ref "U43") (pin "4") (pinfunction "4_4") (pintype "unspecified"))
    )
    (net (code "48") (name "Net-(R81-Pad2)") (class "Default")
      (node (ref "R81") (pin "2") (pinfunction "2_2") (pintype "input"))
      (node (ref "U49") (pin "1") (pinfunction "1_1") (pintype "unspecified"))
    )
    (net (code "49") (name "Net-(R82-Pad2)") (class "Default")
      (node (ref "R82") (pin "2") (pinfunction "2_2") (pintype "input"))
      (node (ref "U49") (pin "2") (pinfunction "2_2") (pintype "unspecified"))
    )
    (net (code "50") (name "Net-(R83-Pad2)") (class "Default")
      (node (ref "R83") (pin "2") (pinfunction "2_2") (pintype "input"))
      (node (ref "U49") (pin "3") (pinfunction "3_3") (pintype "unspecified"))
    )
    (net (code "51") (name "Net-(R84-Pad2)") (class "Default")
      (node (ref "R84") (pin "2") (pinfunction "2_2") (pintype "input"))
      (node (ref "U49") (pin "4") (pinfunction "4_4") (pintype "unspecified"))
    )
    (net (code "52") (name "Net-(R94-Pad1)") (class "Default")
      (node (ref "R94") (pin "1") (pinfunction "1_1") (pintype "input"))
      (node (ref "U65") (pin "2") (pinfunction "2_2") (pintype "input"))
    )
    (net (code "53") (name "Net-(R97-Pad1)") (class "Default")
      (node (ref "R97") (pin "1") (pinfunction "1_1") (pintype "input"))
      (node (ref "U67") (pin "2") (pinfunction "2_2") (pintype "input"))
    )
    (net (code "54") (name "Net-(R100-Pad1)") (class "Default")
      (node (ref "R100") (pin "1") (pinfunction "1_1") (pintype "input"))
      (node (ref "U52") (pin "1") (pinfunction "1_1") (pintype "input"))
    )
    (net (code "55") (name "Net-(R101-Pad1)") (class "Default")
      (node (ref "R101") (pin "1") (pinfunction "1_1") (pintype "input"))
      (node (ref "U48") (pin "1") (pinfunction "1_1") (pintype "input"))
    )
    (net (code "56") (name "Net-(U17-+HV)") (class "Default")
      (node (ref "R2") (pin "2") (pinfunction "2_2") (pintype "input"))
      (node (ref "U17") (pin "4") (pinfunction "+HV_4") (pintype "input"))
    )
    (net (code "57") (name "Net-(U17--HV)") (class "Default")
      (node (ref "U17") (pin "5") (pinfunction "-HV_5") (pintype "input"))
      (node (ref "U55") (pin "1") (pinfunction "1_1") (pintype "input"))
    )
    (net (code "58") (name "Net-(U17-M)") (class "Default")
      (node (ref "R3") (pin "1") (pinfunction "1_1") (pintype "input"))
      (node (ref "R93") (pin "1") (pinfunction "1_1") (pintype "input"))
      (node (ref "U17") (pin "1") (pinfunction "M_1") (pintype "input"))
    )
    (net (code "59") (name "Net-(U21A-1IN+)") (class "Default")
      (node (ref "C45") (pin "1") (pinfunction "1_1") (pintype "input"))
      (node (ref "R93") (pin "2") (pinfunction "2_2") (pintype "input"))
      (node (ref "U21") (pin "3") (pinfunction "1IN+_3") (pintype "unspecified"))
    )
    (net (code "60") (name "Net-(U21A-1IN-)") (class "Default")
      (node (ref "R4") (pin "1") (pinfunction "1_1") (pintype "input"))
      (node (ref "U21") (pin "1") (pinfunction "1OUT_1") (pintype "unspecified"))
      (node (ref "U21") (pin "2") (pinfunction "1IN-_2") (pintype "unspecified"))
    )
    (net (code "61") (name "Net-(U21B-2IN-)") (class "Default")
      (node (ref "R4") (pin "2") (pinfunction "2_2") (pintype "input"))
      (node (ref "R5") (pin "1") (pinfunction "1_1") (pintype "input"))
      (node (ref "R6") (pin "1") (pinfunction "1_1") (pintype "input"))
      (node (ref "R7") (pin "1") (pinfunction "1_1") (pintype "input"))
      (node (ref "R8") (pin "1") (pinfunction "1_1") (pintype "input"))
      (node (ref "U21") (pin "6") (pinfunction "2IN-_6") (pintype "unspecified"))
    )
    (net (code "62") (name "Net-(U21B-2OUT)") (class "Default")
      (node (ref "R9") (pin "1") (pinfunction "1_1") (pintype "input"))
      (node (ref "U21") (pin "7") (pinfunction "2OUT_7") (pintype "unspecified"))
      (node (ref "U5") (pin "5") (pinfunction "5_5") (pintype "unspecified"))
      (node (ref "U5") (pin "6") (pinfunction "6_6") (pintype "unspecified"))
      (node (ref "U5") (pin "7") (pinfunction "7_7") (pintype "unspecified"))
      (node (ref "U5") (pin "8") (pinfunction "8_8") (pintype "unspecified"))
    )
    (net (code "63") (name "Net-(U21C-3IN+)") (class "Default")
      (node (ref "R10") (pin "1") (pinfunction "1_1") (pintype "input"))
      (node (ref "R9") (pin "2") (pinfunction "2_2") (pintype "input"))
      (node (ref "U21") (pin "10") (pinfunction "3IN+_10") (pintype "unspecified"))
    )
    (net (code "64") (name "Net-(U21C-3IN-)") (class "Default")
      (node (ref "R11") (pin "1") (pinfunction "1_1") (pintype "input"))
      (node (ref "U21") (pin "8") (pinfunction "3OUT_8") (pintype "unspecified"))
      (node (ref "U21") (pin "9") (pinfunction "3IN-_9") (pintype "unspecified"))
    )
    (net (code "65") (name "Net-(U21D-4IN+)") (class "Default")
      (node (ref "C1") (pin "1") (pinfunction "1_1") (pintype "input"))
      (node (ref "R12") (pin "2") (pinfunction "2_2") (pintype "input"))
      (node (ref "U21") (pin "12") (pinfunction "4IN+_12") (pintype "unspecified"))
    )
    (net (code "66") (name "Net-(U21D-4IN-)") (class "Default")
      (node (ref "R13") (pin "1") (pinfunction "1_1") (pintype "input"))
      (node (ref "R14") (pin "2") (pinfunction "2_2") (pintype "input"))
      (node (ref "U21") (pin "13") (pinfunction "4IN-_13") (pintype "unspecified"))
    )
    (net (code "67") (name "Net-(U21D-4OUT)") (class "Default")
      (node (ref "R13") (pin "2") (pinfunction "2_2") (pintype "input"))
      (node (ref "U21") (pin "14") (pinfunction "4OUT_14") (pintype "unspecified"))
      (node (ref "U22") (pin "5") (pinfunction "5_5") (pintype "unspecified"))
      (node (ref "U22") (pin "6") (pinfunction "6_6") (pintype "unspecified"))
      (node (ref "U22") (pin "7") (pinfunction "7_7") (pintype "unspecified"))
      (node (ref "U22") (pin "8") (pinfunction "8_8") (pintype "unspecified"))
      (node (ref "U68") (pin "3") (pinfunction "3_3") (pintype "unspecified"))
    )
    (net (code "68") (name "Net-(U24-+Vin)") (class "Default")
      (node (ref "C44") (pin "1") (pinfunction "1_1") (pintype "input"))
      (node (ref "C51") (pin "1") (pinfunction "1_1") (pintype "input"))
      (node (ref "L1") (pin "2") (pinfunction "2_2") (pintype "input"))
      (node (ref "U24") (pin "16") (pinfunction "+Vin_16") (pintype "input"))
      (node (ref "U59") (pin "3") (pinfunction "IN_3") (pintype "unspecified"))
    )
    (net (code "69") (name "Net-(U24--Vin)") (class "Default")
      (node (ref "C44") (pin "2") (pinfunction "2_2") (pintype "input"))
      (node (ref "U24") (pin "1") (pinfunction "-Vin_1") (pintype "input"))
      (node (ref "U62") (pin "4") (pinfunction "V0-_4") (pintype "input"))
    )
    (net (code "70") (name "Net-(U29A-1IN+)") (class "Default")
      (node (ref "C47") (pin "1") (pinfunction "1_1") (pintype "input"))
      (node (ref "R99") (pin "2") (pinfunction "2_2") (pintype "input"))
      (node (ref "U29") (pin "3") (pinfunction "1IN+_3") (pintype "unspecified"))
    )
    (net (code "71") (name "Net-(U29A-1IN-)") (class "Default")
      (node (ref "R17") (pin "1") (pinfunction "1_1") (pintype "input"))
      (node (ref "U29") (pin "1") (pinfunction "1OUT_1") (pintype "unspecified"))
      (node (ref "U29") (pin "2") (pinfunction "1IN-_2") (pintype "unspecified"))
    )
    (net (code "72") (name "Net-(U29B-2IN-)") (class "Default")
      (node (ref "R17") (pin "2") (pinfunction "2_2") (pintype "input"))
      (node (ref "R18") (pin "1") (pinfunction "1_1") (pintype "input"))
      (node (ref "R19") (pin "1") (pinfunction "1_1") (pintype "input"))
      (node (ref "R20") (pin "1") (pinfunction "1_1") (pintype "input"))
      (node (ref "R21") (pin "1") (pinfunction "1_1") (pintype "input"))
      (node (ref "U29") (pin "6") (pinfunction "2IN-_6") (pintype "unspecified"))
    )
    (net (code "73") (name "Net-(U29B-2OUT)") (class "Default")
      (node (ref "R22") (pin "1") (pinfunction "1_1") (pintype "input"))
      (node (ref "U26") (pin "5") (pinfunction "5_5") (pintype "unspecified"))
      (node (ref "U26") (pin "6") (pinfunction "6_6") (pintype "unspecified"))
      (node (ref "U26") (pin "7") (pinfunction "7_7") (pintype "unspecified"))
      (node (ref "U26") (pin "8") (pinfunction "8_8") (pintype "unspecified"))
      (node (ref "U29") (pin "7") (pinfunction "2OUT_7") (pintype "unspecified"))
    )
    (net (code "74") (name "Net-(U29C-3IN+)") (class "Default")
      (node (ref "R22") (pin "2") (pinfunction "2_2") (pintype "input"))
      (node (ref "R23") (pin "1") (pinfunction "1_1") (pintype "input"))
      (node (ref "U29") (pin "10") (pinfunction "3IN+_10") (pintype "unspecified"))
    )
    (net (code "75") (name "Net-(U29C-3IN-)") (class "Default")
      (node (ref "R24") (pin "1") (pinfunction "1_1") (pintype "input"))
      (node (ref "U29") (pin "8") (pinfunction "3OUT_8") (pintype "unspecified"))
      (node (ref "U29") (pin "9") (pinfunction "3IN-_9") (pintype "unspecified"))
    )
    (net (code "76") (name "Net-(U29D-4IN+)") (class "Default")
      (node (ref "C12") (pin "1") (pinfunction "1_1") (pintype "input"))
      (node (ref "R25") (pin "2") (pinfunction "2_2") (pintype "input"))
      (node (ref "U29") (pin "12") (pinfunction "4IN+_12") (pintype "unspecified"))
    )
    (net (code "77") (name "Net-(U29D-4IN-)") (class "Default")
      (node (ref "R26") (pin "1") (pinfunction "1_1") (pintype "input"))
      (node (ref "R27") (pin "2") (pinfunction "2_2") (pintype "input"))
      (node (ref "U29") (pin "13") (pinfunction "4IN-_13") (pintype "unspecified"))
    )
    (net (code "78") (name "Net-(U29D-4OUT)") (class "Default")
      (node (ref "R26") (pin "2") (pinfunction "2_2") (pintype "input"))
      (node (ref "U28") (pin "5") (pinfunction "5_5") (pintype "unspecified"))
      (node (ref "U28") (pin "6") (pinfunction "6_6") (pintype "unspecified"))
      (node (ref "U28") (pin "7") (pinfunction "7_7") (pintype "unspecified"))
      (node (ref "U28") (pin "8") (pinfunction "8_8") (pintype "unspecified"))
      (node (ref "U29") (pin "14") (pinfunction "4OUT_14") (pintype "unspecified"))
      (node (ref "U70") (pin "3") (pinfunction "3_3") (pintype "unspecified"))
    )
    (net (code "79") (name "Net-(U33A-1IN+)") (class "Default")
      (node (ref "C46") (pin "1") (pinfunction "1_1") (pintype "input"))
      (node (ref "R96") (pin "2") (pinfunction "2_2") (pintype "input"))
      (node (ref "U33") (pin "3") (pinfunction "1IN+_3") (pintype "unspecified"))
    )
    (net (code "80") (name "Net-(U33A-1IN-)") (class "Default")
      (node (ref "R30") (pin "1") (pinfunction "1_1") (pintype "input"))
      (node (ref "U33") (pin "1") (pinfunction "1OUT_1") (pintype "unspecified"))
      (node (ref "U33") (pin "2") (pinfunction "1IN-_2") (pintype "unspecified"))
    )
    (net (code "81") (name "Net-(U33B-2IN-)") (class "Default")
      (node (ref "R30") (pin "2") (pinfunction "2_2") (pintype "input"))
      (node (ref "R31") (pin "1") (pinfunction "1_1") (pintype "input"))
      (node (ref "R32") (pin "1") (pinfunction "1_1") (pintype "input"))
      (node (ref "R33") (pin "1") (pinfunction "1_1") (pintype "input"))
      (node (ref "R34") (pin "1") (pinfunction "1_1") (pintype "input"))
      (node (ref "U33") (pin "6") (pinfunction "2IN-_6") (pintype "unspecified"))
    )
    (net (code "82") (name "Net-(U33B-2OUT)") (class "Default")
      (node (ref "R35") (pin "1") (pinfunction "1_1") (pintype "input"))
      (node (ref "U30") (pin "5") (pinfunction "5_5") (pintype "unspecified"))
      (node (ref "U30") (pin "6") (pinfunction "6_6") (pintype "unspecified"))
      (node (ref "U30") (pin "7") (pinfunction "7_7") (pintype "unspecified"))
      (node (ref "U30") (pin "8") (pinfunction "8_8") (pintype "unspecified"))
      (node (ref "U33") (pin "7") (pinfunction "2OUT_7") (pintype "unspecified"))
    )
    (net (code "83") (name "Net-(U33C-3IN+)") (class "Default")
      (node (ref "R35") (pin "2") (pinfunction "2_2") (pintype "input"))
      (node (ref "R36") (pin "1") (pinfunction "1_1") (pintype "input"))
      (node (ref "U33") (pin "10") (pinfunction "3IN+_10") (pintype "unspecified"))
    )
    (net (code "84") (name "Net-(U33C-3IN-)") (class "Default")
      (node (ref "R37") (pin "1") (pinfunction "1_1") (pintype "input"))
      (node (ref "U33") (pin "8") (pinfunction "3OUT_8") (pintype "unspecified"))
      (node (ref "U33") (pin "9") (pinfunction "3IN-_9") (pintype "unspecified"))
    )
    (net (code "85") (name "Net-(U33D-4IN+)") (class "Default")
      (node (ref "C17") (pin "1") (pinfunction "1_1") (pintype "input"))
      (node (ref "R38") (pin "2") (pinfunction "2_2") (pintype "input"))
      (node (ref "U33") (pin "12") (pinfunction "4IN+_12") (pintype "unspecified"))
    )
    (net (code "86") (name "Net-(U33D-4IN-)") (class "Default")
      (node (ref "R39") (pin "1") (pinfunction "1_1") (pintype "input"))
      (node (ref "R40") (pin "2") (pinfunction "2_2") (pintype "input"))
      (node (ref "U33") (pin "13") (pinfunction "4IN-_13") (pintype "unspecified"))
    )
    (net (code "87") (name "Net-(U33D-4OUT)") (class "Default")
      (node (ref "R39") (pin "2") (pinfunction "2_2") (pintype "input"))
      (node (ref "U32") (pin "5") (pinfunction "5_5") (pintype "unspecified"))
      (node (ref "U32") (pin "6") (pinfunction "6_6") (pintype "unspecified"))
      (node (ref "U32") (pin "7") (pinfunction "7_7") (pintype "unspecified"))
      (node (ref "U32") (pin "8") (pinfunction "8_8") (pintype "unspecified"))
      (node (ref "U33") (pin "14") (pinfunction "4OUT_14") (pintype "unspecified"))
      (node (ref "U69") (pin "3") (pinfunction "3_3") (pintype "unspecified"))
    )
    (net (code "88") (name "Net-(U46A-1IN+)") (class "Default")
      (node (ref "C49") (pin "1") (pinfunction "1_1") (pintype "input"))
      (node (ref "R101") (pin "2") (pinfunction "2_2") (pintype "input"))
      (node (ref "U46") (pin "3") (pinfunction "1IN+_3") (pintype "unspecified"))
    )
    (net (code "89") (name "Net-(U46A-1IN-)") (class "Default")
      (node (ref "R68") (pin "1") (pinfunction "1_1") (pintype "input"))
      (node (ref "U46") (pin "1") (pinfunction "1OUT_1") (pintype "unspecified"))
      (node (ref "U46") (pin "2") (pinfunction "1IN-_2") (pintype "unspecified"))
    )
    (net (code "90") (name "Net-(U46B-2IN-)") (class "Default")
      (node (ref "R68") (pin "2") (pinfunction "2_2") (pintype "input"))
      (node (ref "R69") (pin "1") (pinfunction "1_1") (pintype "input"))
      (node (ref "R70") (pin "1") (pinfunction "1_1") (pintype "input"))
      (node (ref "R71") (pin "1") (pinfunction "1_1") (pintype "input"))
      (node (ref "R72") (pin "1") (pinfunction "1_1") (pintype "input"))
      (node (ref "U46") (pin "6") (pinfunction "2IN-_6") (pintype "unspecified"))
    )
    (net (code "91") (name "Net-(U46B-2OUT)") (class "Default")
      (node (ref "R73") (pin "1") (pinfunction "1_1") (pintype "input"))
      (node (ref "U43") (pin "5") (pinfunction "5_5") (pintype "unspecified"))
      (node (ref "U43") (pin "6") (pinfunction "6_6") (pintype "unspecified"))
      (node (ref "U43") (pin "7") (pinfunction "7_7") (pintype "unspecified"))
      (node (ref "U43") (pin "8") (pinfunction "8_8") (pintype "unspecified"))
      (node (ref "U46") (pin "7") (pinfunction "2OUT_7") (pintype "unspecified"))
    )
    (net (code "92") (name "Net-(U46C-3IN+)") (class "Default")
      (node (ref "R73") (pin "2") (pinfunction "2_2") (pintype "input"))
      (node (ref "R74") (pin "1") (pinfunction "1_1") (pintype "input"))
      (node (ref "U46") (pin "10") (pinfunction "3IN+_10") (pintype "unspecified"))
    )
    (net (code "93") (name "Net-(U46C-3IN-)") (class "Default")
      (node (ref "R75") (pin "1") (pinfunction "1_1") (pintype "input"))
      (node (ref "U46") (pin "8") (pinfunction "3OUT_8") (pintype "unspecified"))
      (node (ref "U46") (pin "9") (pinfunction "3IN-_9") (pintype "unspecified"))
    )
    (net (code "94") (name "Net-(U46D-4IN+)") (class "Default")
      (node (ref "C32") (pin "1") (pinfunction "1_1") (pintype "input"))
      (node (ref "R76") (pin "2") (pinfunction "2_2") (pintype "input"))
      (node (ref "U46") (pin "12") (pinfunction "4IN+_12") (pintype "unspecified"))
    )
    (net (code "95") (name "Net-(U46D-4IN-)") (class "Default")
      (node (ref "R77") (pin "1") (pinfunction "1_1") (pintype "input"))
      (node (ref "R78") (pin "2") (pinfunction "2_2") (pintype "input"))
      (node (ref "U46") (pin "13") (pinfunction "4IN-_13") (pintype "unspecified"))
    )
    (net (code "96") (name "Net-(U46D-4OUT)") (class "Default")
      (node (ref "R77") (pin "2") (pinfunction "2_2") (pintype "input"))
      (node (ref "U44") (pin "5") (pinfunction "5_5") (pintype "unspecified"))
      (node (ref "U44") (pin "6") (pinfunction "6_6") (pintype "unspecified"))
      (node (ref "U44") (pin "7") (pinfunction "7_7") (pintype "unspecified"))
      (node (ref "U44") (pin "8") (pinfunction "8_8") (pintype "unspecified"))
      (node (ref "U46") (pin "14") (pinfunction "4OUT_14") (pintype "unspecified"))
      (node (ref "U71") (pin "3") (pinfunction "3_3") (pintype "unspecified"))
    )
    (net (code "97") (name "Net-(U53A-1IN+)") (class "Default")
      (node (ref "C48") (pin "1") (pinfunction "1_1") (pintype "input"))
      (node (ref "R100") (pin "2") (pinfunction "2_2") (pintype "input"))
      (node (ref "U53") (pin "3") (pinfunction "1IN+_3") (pintype "unspecified"))
    )
    (net (code "98") (name "Net-(U53A-1IN-)") (class "Default")
      (node (ref "R80") (pin "1") (pinfunction "1_1") (pintype "input"))
      (node (ref "U53") (pin "1") (pinfunction "1OUT_1") (pintype "unspecified"))
      (node (ref "U53") (pin "2") (pinfunction "1IN-_2") (pintype "unspecified"))
    )
    (net (code "99") (name "Net-(U53B-2IN-)") (class "Default")
      (node (ref "R80") (pin "2") (pinfunction "2_2") (pintype "input"))
      (node (ref "R81") (pin "1") (pinfunction "1_1") (pintype "input"))
      (node (ref "R82") (pin "1") (pinfunction "1_1") (pintype "input"))
      (node (ref "R83") (pin "1") (pinfunction "1_1") (pintype "input"))
      (node (ref "R84") (pin "1") (pinfunction "1_1") (pintype "input"))
      (node (ref "U53") (pin "6") (pinfunction "2IN-_6") (pintype "unspecified"))
    )
    (net (code "100") (name "Net-(U53B-2OUT)") (class "Default")
      (node (ref "R85") (pin "1") (pinfunction "1_1") (pintype "input"))
      (node (ref "U49") (pin "5") (pinfunction "5_5") (pintype "unspecified"))
      (node (ref "U49") (pin "6") (pinfunction "6_6") (pintype "unspecified"))
      (node (ref "U49") (pin "7") (pinfunction "7_7") (pintype "unspecified"))
      (node (ref "U49") (pin "8") (pinfunction "8_8") (pintype "unspecified"))
      (node (ref "U53") (pin "7") (pinfunction "2OUT_7") (pintype "unspecified"))
    )
    (net (code "101") (name "Net-(U53C-3IN+)") (class "Default")
      (node (ref "R85") (pin "2") (pinfunction "2_2") (pintype "input"))
      (node (ref "R86") (pin "1") (pinfunction "1_1") (pintype "input"))
      (node (ref "U53") (pin "10") (pinfunction "3IN+_10") (pintype "unspecified"))
    )
    (net (code "102") (name "Net-(U53C-3IN-)") (class "Default")
      (node (ref "R87") (pin "1") (pinfunction "1_1") (pintype "input"))
      (node (ref "U53") (pin "8") (pinfunction "3OUT_8") (pintype "unspecified"))
      (node (ref "U53") (pin "9") (pinfunction "3IN-_9") (pintype "unspecified"))
    )
    (net (code "103") (name "Net-(U53D-4IN+)") (class "Default")
      (node (ref "C37") (pin "1") (pinfunction "1_1") (pintype "input"))
      (node (ref "R88") (pin "2") (pinfunction "2_2") (pintype "input"))
      (node (ref "U53") (pin "12") (pinfunction "4IN+_12") (pintype "unspecified"))
    )
    (net (code "104") (name "Net-(U53D-4IN-)") (class "Default")
      (node (ref "R89") (pin "1") (pinfunction "1_1") (pintype "input"))
      (node (ref "R90") (pin "2") (pinfunction "2_2") (pintype "input"))
      (node (ref "U53") (pin "13") (pinfunction "4IN-_13") (pintype "unspecified"))
    )
    (net (code "105") (name "Net-(U53D-4OUT)") (class "Default")
      (node (ref "R89") (pin "2") (pinfunction "2_2") (pintype "input"))
      (node (ref "U50") (pin "5") (pinfunction "5_5") (pintype "unspecified"))
      (node (ref "U50") (pin "6") (pinfunction "6_6") (pintype "unspecified"))
      (node (ref "U50") (pin "7") (pinfunction "7_7") (pintype "unspecified"))
      (node (ref "U50") (pin "8") (pinfunction "8_8") (pintype "unspecified"))
      (node (ref "U53") (pin "14") (pinfunction "4OUT_14") (pintype "unspecified"))
      (node (ref "U72") (pin "3") (pinfunction "3_3") (pintype "unspecified"))
    )
    (net (code "106") (name "Net-(U59-ADJ)") (class "Default")
      (node (ref "R91") (pin "2") (pinfunction "2_2") (pintype "input"))
      (node (ref "R92") (pin "1") (pinfunction "1_1") (pintype "input"))
      (node (ref "U59") (pin "1") (pinfunction "ADJ_1") (pintype "unspecified"))
    )
    (net (code "107") (name "Net-(U62-L)") (class "Default")
      (node (ref "F1") (pin "2") (pinfunction "2_2") (pintype "unspecified"))
      (node (ref "R113") (pin "2") (pinfunction "2_2") (pintype "unspecified"))
      (node (ref "U62") (pin "1") (pinfunction "L_1") (pintype "input"))
    )
    (net (code "108") (name "Net-(U62-N)") (class "Default")
      (node (ref "R113") (pin "1") (pinfunction "1_1") (pintype "unspecified"))
      (node (ref "U57") (pin "2") (pinfunction "2_2") (pintype "input"))
      (node (ref "U62") (pin "2") (pinfunction "N_2") (pintype "input"))
    )
    (net (code "109") (name "Net-(U62-V0+)") (class "Default")
      (node (ref "L1") (pin "1") (pinfunction "1_1") (pintype "input"))
      (node (ref "U62") (pin "5") (pinfunction "V0+_5") (pintype "input"))
    )
    (net (code "110") (name "Net-(U64-+HV)") (class "Default")
      (node (ref "R94") (pin "2") (pinfunction "2_2") (pintype "input"))
      (node (ref "U64") (pin "4") (pinfunction "+HV_4") (pintype "input"))
    )
    (net (code "111") (name "Net-(U64--HV)") (class "Default")
      (node (ref "U64") (pin "5") (pinfunction "-HV_5") (pintype "input"))
      (node (ref "U65") (pin "1") (pinfunction "1_1") (pintype "input"))
    )
    (net (code "112") (name "Net-(U64-M)") (class "Default")
      (node (ref "R95") (pin "1") (pinfunction "1_1") (pintype "input"))
      (node (ref "R96") (pin "1") (pinfunction "1_1") (pintype "input"))
      (node (ref "U64") (pin "1") (pinfunction "M_1") (pintype "input"))
    )
    (net (code "113") (name "Net-(U66-+HV)") (class "Default")
      (node (ref "R97") (pin "2") (pinfunction "2_2") (pintype "input"))
      (node (ref "U66") (pin "4") (pinfunction "+HV_4") (pintype "input"))
    )
    (net (code "114") (name "Net-(U66--HV)") (class "Default")
      (node (ref "U66") (pin "5") (pinfunction "-HV_5") (pintype "input"))
      (node (ref "U67") (pin "1") (pinfunction "1_1") (pintype "input"))
    )
    (net (code "115") (name "Net-(U66-M)") (class "Default")
      (node (ref "R98") (pin "1") (pinfunction "1_1") (pintype "input"))
      (node (ref "R99") (pin "1") (pinfunction "1_1") (pintype "input"))
      (node (ref "U66") (pin "1") (pinfunction "M_1") (pintype "input"))
    )
    (net (code "116") (name "unconnected-(U62-FG-Pad3)") (class "Default")
      (node (ref "U62") (pin "3") (pinfunction "FG_3") (pintype "input"))
    )
    (net (code "117") (name "unconnected-(U90-Pad1)") (class "Default")
      (node (ref "U90") (pin "1") (pinfunction "1_1") (pintype "unspecified"))
    )
    (net (code "118") (name "unconnected-(U90-Pad2)") (class "Default")
      (node (ref "U90") (pin "2") (pinfunction "2_2") (pintype "unspecified"))
    )
    (net (code "119") (name "unconnected-(U90-Pad3)") (class "Default")
      (node (ref "U90") (pin "3") (pinfunction "3_3") (pintype "unspecified"))
    )
    (net (code "120") (name "unconnected-(U90-Pad4)") (class "Default")
      (node (ref "U90") (pin "4") (pinfunction "4_4") (pintype "unspecified"))
    )
    (net (code "121") (name "unconnected-(U90-Pad5)") (class "Default")
      (node (ref "U90") (pin "5") (pinfunction "5_5") (pintype "unspecified"))
    )
    (net (code "122") (name "unconnected-(U90-Pad6)") (class "Default")
      (node (ref "U90") (pin "6") (pinfunction "6_6") (pintype "unspecified"))
    )
    (net (code "123") (name "unconnected-(U91-Pad1)") (class "Default")
      (node (ref "U91") (pin "1") (pinfunction "1_1") (pintype "input"))
    )
    (net (code "124") (name "unconnected-(U91-Pad2)") (class "Default")
      (node (ref "U91") (pin "2") (pinfunction "2_2") (pintype "input"))
    )
    (net (code "125") (name "unconnected-(U92-Pad1)") (class "Default")
      (node (ref "U92") (pin "1") (pinfunction "1_1") (pintype "unspecified"))
    )
    (net (code "126") (name "unconnected-(U92-Pad2)") (class "Default")
      (node (ref "U92") (pin "2") (pinfunction "2_2") (pintype "unspecified"))
    )
    (net (code "127") (name "unconnected-(U92-Pad3)") (class "Default")
      (node (ref "U92") (pin "3") (pinfunction "3_3") (pintype "unspecified"))
    )
    (net (code "128") (name "unconnected-(U92-Pad4)") (class "Default")
      (node (ref "U92") (pin "4") (pinfunction "4_4") (pintype "unspecified"))
    )
  )
)
